# ADQ_DIP.net
KiCad netlist of a schematic drawn in EAGLE
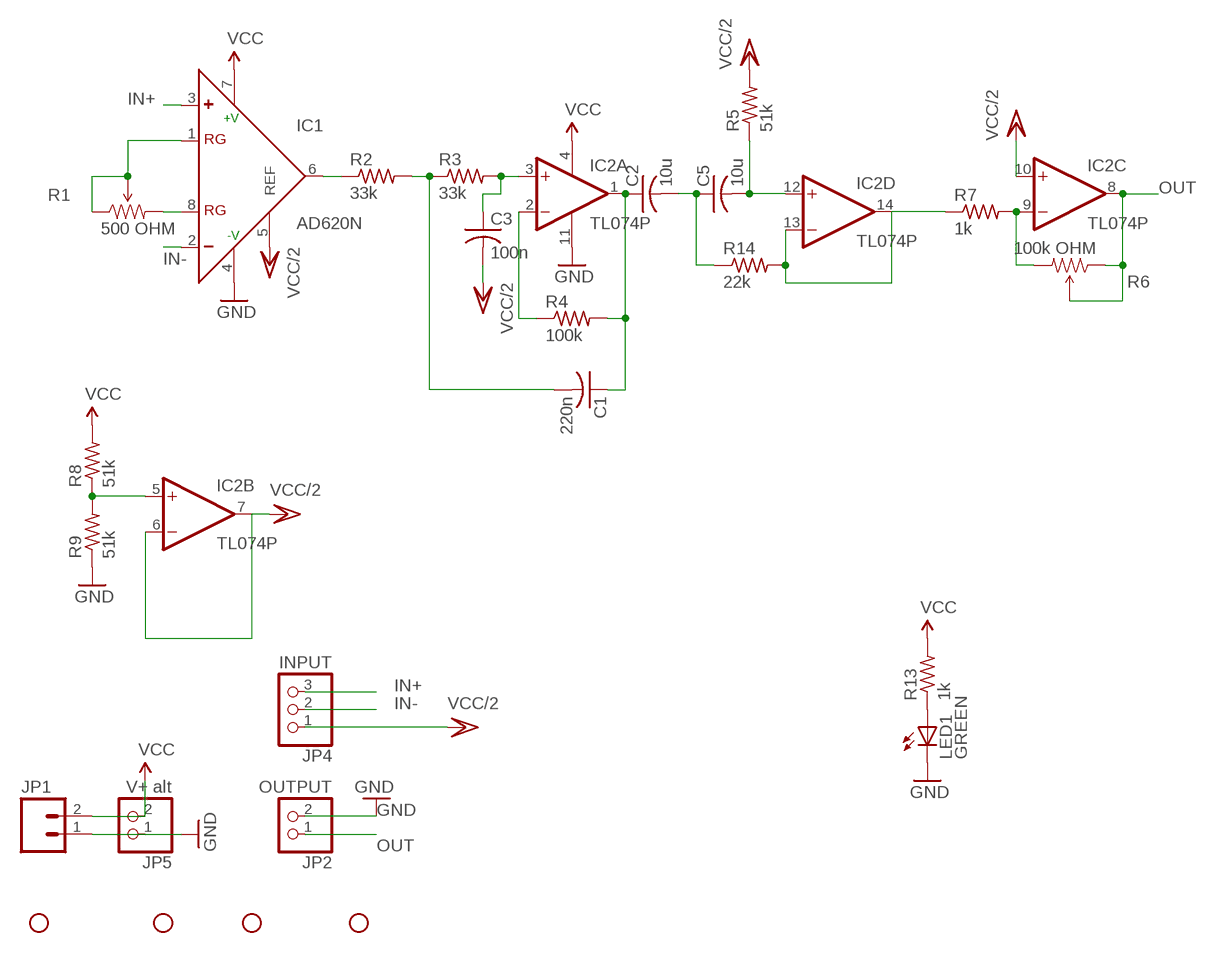
[diagram p0: schematic, sheet 1]

(export (version "E")
  (design (tool "Eeschema 10.0.6"))
  (components
    (comp (ref "C1")
      (value "220n")
      (footprint "eagle-import:C0805")
      (libsource (lib "eagle-import") (part "C-USC0805"))
    )
    (comp (ref "C2")
      (value "10u")
      (footprint "eagle-import:C0805")
      (libsource (lib "eagle-import") (part "C-USC0805"))
    )
    (comp (ref "C3")
      (value "100n")
      (footprint "eagle-import:C0805")
      (libsource (lib "eagle-import") (part "C-USC0805"))
    )
    (comp (ref "C5")
      (value "10u")
      (footprint "eagle-import:C0805")
      (libsource (lib "eagle-import") (part "C-USC0805"))
    )
    (comp (ref "IC1")
      (value "AD620N")
      (footprint "eagle-import:DIL08")
      (fields
        (field (name "MF") "ALTERA CORPORATION")
        (field (name "MPN") "AD620AN")
        (field (name "MF_1") "ALTERA CORPORATION")
        (field (name "MPN_1") "AD620AN")
        (field (name "OC_FARNELL") "1523782")
        (field (name "OC_NEWARK") "05F7108")
      )
      (libsource (lib "eagle-import") (part "AD620N"))
    )
    (comp (ref "IC2")
      (value "TL074P")
      (footprint "eagle-import:DIL14")
      (libsource (lib "eagle-import") (part "TL074P"))
    )
    (comp (ref "JP1")
      (value "M02JST-PTH-2")
      (footprint "eagle-import:JST-2-PTH")
      (libsource (lib "eagle-import") (part "M02JST-PTH-2"))
    )
    (comp (ref "JP2")
      (value "OUTPUT")
      (footprint "eagle-import:1X02")
      (libsource (lib "eagle-import") (part "PINHD-1X2"))
    )
    (comp (ref "JP3")
      (value "STAND-OFF")
      (footprint "eagle-import:STAND-OFF")
      (libsource (lib "eagle-import") (part "STAND-OFF"))
    )
    (comp (ref "JP4")
      (value "INPUT")
      (footprint "eagle-import:1X03")
      (libsource (lib "eagle-import") (part "PINHD-1X3"))
    )
    (comp (ref "JP5")
      (value "V+ alt")
      (footprint "eagle-import:1X02")
      (libsource (lib "eagle-import") (part "PINHD-1X2"))
    )
    (comp (ref "JP6")
      (value "STAND-OFF")
      (footprint "eagle-import:STAND-OFF")
      (libsource (lib "eagle-import") (part "STAND-OFF"))
    )
    (comp (ref "JP7")
      (value "STAND-OFF")
      (footprint "eagle-import:STAND-OFF")
      (libsource (lib "eagle-import") (part "STAND-OFF"))
    )
    (comp (ref "JP8")
      (value "STAND-OFF")
      (footprint "eagle-import:STAND-OFF")
      (libsource (lib "eagle-import") (part "STAND-OFF"))
    )
    (comp (ref "LED1")
      (value "GREEN")
      (footprint "eagle-import:CHIPLED_0805")
      (libsource (lib "eagle-import") (part "LEDCHIPLED_0805"))
    )
    (comp (ref "R1")
      (value "500 OHM")
      (footprint "eagle-import:3362U-2")
      (libsource (lib "eagle-import") (part "TRIMPOT"))
    )
    (comp (ref "R2")
      (value "33k")
      (footprint "eagle-import:R1206")
      (libsource (lib "eagle-import") (part "R-US_R1206"))
    )
    (comp (ref "R3")
      (value "33k")
      (footprint "eagle-import:R1206")
      (libsource (lib "eagle-import") (part "R-US_R1206"))
    )
    (comp (ref "R4")
      (value "100k")
      (footprint "eagle-import:R1206")
      (libsource (lib "eagle-import") (part "R-US_R1206"))
    )
    (comp (ref "R5")
      (value "51k")
      (footprint "eagle-import:R1206")
      (libsource (lib "eagle-import") (part "R-US_R1206"))
    )
    (comp (ref "R6")
      (value "100k OHM")
      (footprint "eagle-import:3362U-2")
      (libsource (lib "eagle-import") (part "TRIMPOT"))
    )
    (comp (ref "R7")
      (value "1k")
      (footprint "eagle-import:R1206")
      (libsource (lib "eagle-import") (part "R-US_R1206"))
    )
    (comp (ref "R8")
      (value "51k")
      (footprint "eagle-import:R1206")
      (libsource (lib "eagle-import") (part "R-US_R1206"))
    )
    (comp (ref "R9")
      (value "51k")
      (footprint "eagle-import:R1206")
      (libsource (lib "eagle-import") (part "R-US_R1206"))
    )
    (comp (ref "R13")
      (value "1k")
      (footprint "eagle-import:R1206")
      (libsource (lib "eagle-import") (part "R-US_R1206"))
    )
    (comp (ref "R14")
      (value "22k")
      (footprint "eagle-import:R1206")
      (libsource (lib "eagle-import") (part "R-US_R1206"))
    )
  )
  (nets
    (net (code "1") (name "/IN+") (class "Default")
      (node (ref "IC1") (pin "3") (pinfunction "+_3") (pintype "input"))
      (node (ref "JP4") (pin "3") (pinfunction "3_3") (pintype "passive"))
    )
    (net (code "2") (name "/IN-") (class "Default")
      (node (ref "IC1") (pin "2") (pinfunction "-_2") (pintype "input"))
      (node (ref "JP4") (pin "2") (pinfunction "2_2") (pintype "passive"))
    )
    (net (code "3") (name "/OUT") (class "Default")
      (node (ref "IC2") (pin "8") (pinfunction "OUT_8") (pintype "output"))
      (node (ref "JP2") (pin "1") (pinfunction "1_1") (pintype "passive"))
      (node (ref "R6") (pin "1") (pinfunction "CCW_1") (pintype "passive"))
      (node (ref "R6") (pin "2") (pinfunction "WIPER_2") (pintype "passive"))
    )
    (net (code "4") (name "GND") (class "Default")
      (node (ref "IC1") (pin "4") (pinfunction "-V_4") (pintype "power_in"))
      (node (ref "IC2") (pin "11") (pinfunction "V-_11") (pintype "power_in"))
      (node (ref "JP1") (pin "1") (pinfunction "1_1") (pintype "passive"))
      (node (ref "JP2") (pin "2") (pinfunction "2_2") (pintype "passive"))
      (node (ref "JP5") (pin "1") (pinfunction "1_1") (pintype "passive"))
      (node (ref "LED1") (pin "C") (pinfunction "C_C") (pintype "passive"))
      (node (ref "R9") (pin "1") (pinfunction "1_1") (pintype "passive"))
    )
    (net (code "5") (name "Net-(C1-Pad2)") (class "Default")
      (node (ref "C1") (pin "2") (pinfunction "2_2") (pintype "passive"))
      (node (ref "R2") (pin "2") (pinfunction "2_2") (pintype "passive"))
      (node (ref "R3") (pin "1") (pinfunction "1_1") (pintype "passive"))
    )
    (net (code "6") (name "Net-(C2-Pad2)") (class "Default")
      (node (ref "C2") (pin "2") (pinfunction "2_2") (pintype "passive"))
      (node (ref "C5") (pin "1") (pinfunction "1_1") (pintype "passive"))
      (node (ref "R14") (pin "1") (pinfunction "1_1") (pintype "passive"))
    )
    (net (code "7") (name "Net-(IC1-OUT)") (class "Default")
      (node (ref "IC1") (pin "6") (pinfunction "OUT_6") (pintype "output"))
      (node (ref "R2") (pin "1") (pinfunction "1_1") (pintype "passive"))
    )
    (net (code "8") (name "Net-(IC2A-+IN)") (class "Default")
      (node (ref "C3") (pin "1") (pinfunction "1_1") (pintype "passive"))
      (node (ref "IC2") (pin "3") (pinfunction "+IN_3") (pintype "input"))
      (node (ref "R3") (pin "2") (pinfunction "2_2") (pintype "passive"))
    )
    (net (code "9") (name "Net-(IC2A--IN)") (class "Default")
      (node (ref "IC2") (pin "2") (pinfunction "-IN_2") (pintype "input"))
      (node (ref "R4") (pin "1") (pinfunction "1_1") (pintype "passive"))
    )
    (net (code "10") (name "Net-(IC2A-OUT)") (class "Default")
      (node (ref "C1") (pin "1") (pinfunction "1_1") (pintype "passive"))
      (node (ref "C2") (pin "1") (pinfunction "1_1") (pintype "passive"))
      (node (ref "IC2") (pin "1") (pinfunction "OUT_1") (pintype "output"))
      (node (ref "R4") (pin "2") (pinfunction "2_2") (pintype "passive"))
    )
    (net (code "11") (name "Net-(IC2B-+IN)") (class "Default")
      (node (ref "IC2") (pin "5") (pinfunction "+IN_5") (pintype "input"))
      (node (ref "R8") (pin "1") (pinfunction "1_1") (pintype "passive"))
      (node (ref "R9") (pin "2") (pinfunction "2_2") (pintype "passive"))
    )
    (net (code "12") (name "Net-(IC2C--IN)") (class "Default")
      (node (ref "IC2") (pin "9") (pinfunction "-IN_9") (pintype "input"))
      (node (ref "R6") (pin "3") (pinfunction "CW_3") (pintype "passive"))
      (node (ref "R7") (pin "2") (pinfunction "2_2") (pintype "passive"))
    )
    (net (code "13") (name "Net-(IC2D-+IN)") (class "Default")
      (node (ref "C5") (pin "2") (pinfunction "2_2") (pintype "passive"))
      (node (ref "IC2") (pin "12") (pinfunction "+IN_12") (pintype "input"))
      (node (ref "R5") (pin "1") (pinfunction "1_1") (pintype "passive"))
    )
    (net (code "14") (name "Net-(IC2D--IN)") (class "Default")
      (node (ref "IC2") (pin "13") (pinfunction "-IN_13") (pintype "input"))
      (node (ref "IC2") (pin "14") (pinfunction "OUT_14") (pintype "output"))
      (node (ref "R14") (pin "2") (pinfunction "2_2") (pintype "passive"))
      (node (ref "R7") (pin "1") (pinfunction "1_1") (pintype "passive"))
    )
    (net (code "15") (name "Net-(LED1-PadA)") (class "Default")
      (node (ref "LED1") (pin "A") (pinfunction "A_A") (pintype "passive"))
      (node (ref "R13") (pin "1") (pinfunction "1_1") (pintype "passive"))
    )
    (net (code "16") (name "Net-(R1-CCW)") (class "Default")
      (node (ref "IC1") (pin "1") (pinfunction "RG_1") (pintype "passive"))
      (node (ref "R1") (pin "1") (pinfunction "CCW_1") (pintype "passive"))
      (node (ref "R1") (pin "2") (pinfunction "WIPER_2") (pintype "passive"))
    )
    (net (code "17") (name "Net-(R1-CW)") (class "Default")
      (node (ref "IC1") (pin "8") (pinfunction "RG_8") (pintype "passive"))
      (node (ref "R1") (pin "3") (pinfunction "CW_3") (pintype "passive"))
    )
    (net (code "18") (name "VCC") (class "Default")
      (node (ref "IC1") (pin "7") (pinfunction "+V_7") (pintype "power_in"))
      (node (ref "IC2") (pin "4") (pinfunction "V+_4") (pintype "power_in"))
      (node (ref "JP1") (pin "2") (pinfunction "2_2") (pintype "passive"))
      (node (ref "JP5") (pin "2") (pinfunction "2_2") (pintype "passive"))
      (node (ref "R13") (pin "2") (pinfunction "2_2") (pintype "passive"))
      (node (ref "R8") (pin "2") (pinfunction "2_2") (pintype "passive"))
    )
    (net (code "19") (name "VCC{slash}2") (class "Default")
      (node (ref "C3") (pin "2") (pinfunction "2_2") (pintype "passive"))
      (node (ref "IC1") (pin "5") (pinfunction "REF_5") (pintype "passive"))
      (node (ref "IC2") (pin "10") (pinfunction "+IN_10") (pintype "input"))
      (node (ref "IC2") (pin "6") (pinfunction "-IN_6") (pintype "input"))
      (node (ref "IC2") (pin "7") (pinfunction "OUT_7") (pintype "output"))
      (node (ref "JP4") (pin "1") (pinfunction "1_1") (pintype "passive"))
      (node (ref "R5") (pin "2") (pinfunction "2_2") (pintype "passive"))
    )
  )
)
